# Pucati.net
KiCad netlist of a schematic drawn in EAGLE
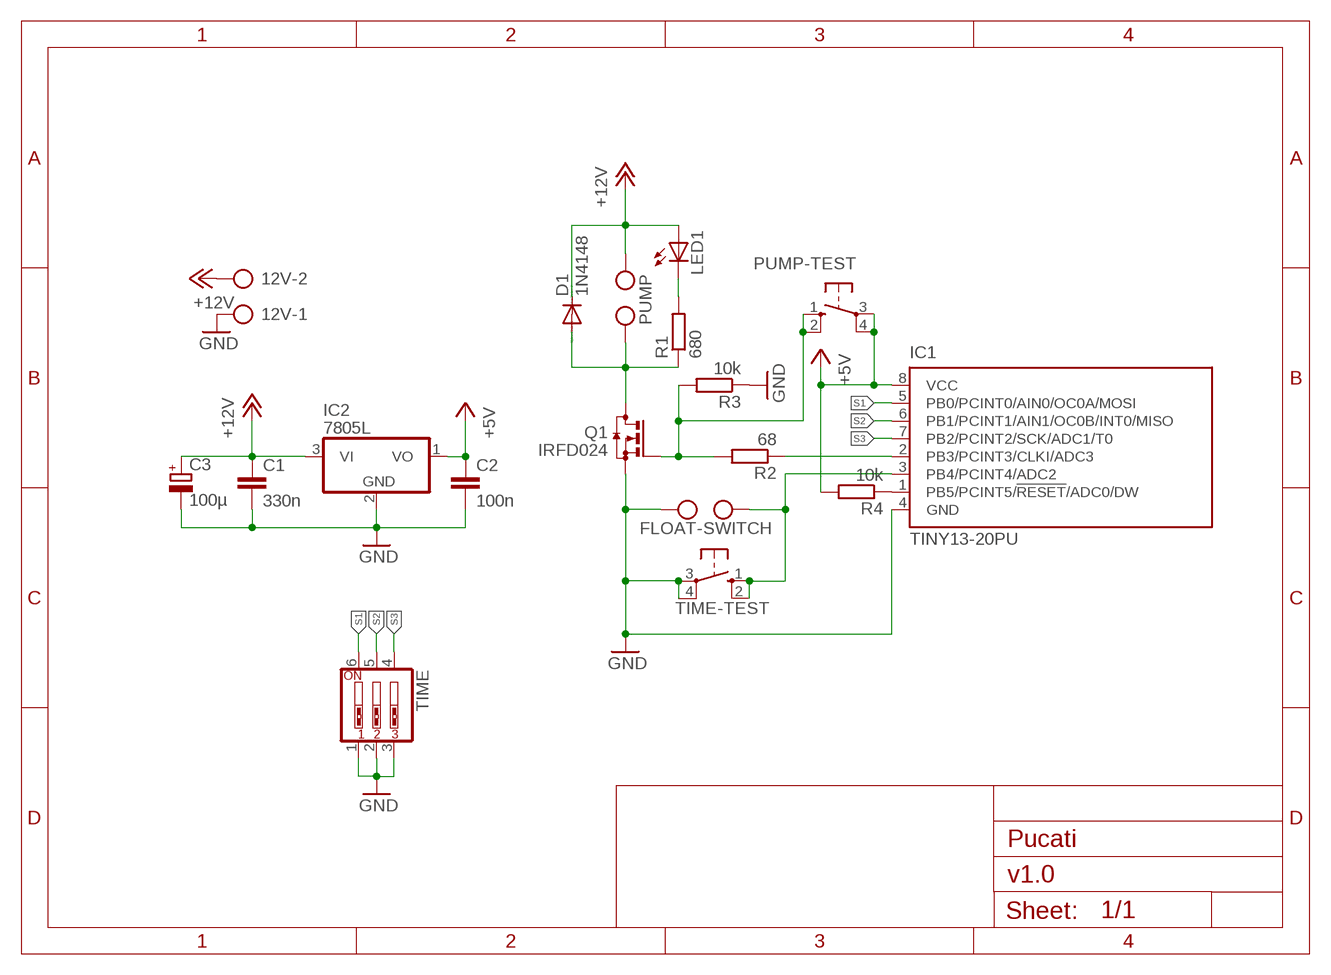
[diagram p0: schematic, sheet 1]

(export (version "E")
  (design (tool "Eeschema 10.0.6"))
  (components
    (comp (ref "12V")
      (value "AK500/2")
      (footprint "eagle-import:AK500_2")
      (libsource (lib "eagle-import") (part "AK500/2"))
    )
    (comp (ref "C1")
      (value "330n")
      (footprint "eagle-import:C1206")
      (libsource (lib "eagle-import") (part "C-EUC1206"))
    )
    (comp (ref "C2")
      (value "100n")
      (footprint "eagle-import:C1206")
      (libsource (lib "eagle-import") (part "C-EUC1206"))
    )
    (comp (ref "C3")
      (value "100µ")
      (footprint "eagle-import:E2,5-5")
      (libsource (lib "eagle-import") (part "CPOL-EUE2.5-5"))
    )
    (comp (ref "D1")
      (value "1N4148")
      (footprint "eagle-import:DO35-10")
      (libsource (lib "eagle-import") (part "1N4148DO35-10"))
    )
    (comp (ref "FLOAT-SWITCH")
      (value "AK500/2")
      (footprint "eagle-import:AK500_2")
      (libsource (lib "eagle-import") (part "AK500/2"))
    )
    (comp (ref "IC1")
      (value "TINY13-20PU")
      (footprint "eagle-import:DIL08")
      (fields (field (name "MPN") "ATTINY13-20PU"))
      (libsource (lib "eagle-import") (part "TINY13PU-20"))
    )
    (comp (ref "IC2")
      (value "7805L")
      (footprint "eagle-import:TO92")
      (libsource (lib "eagle-import") (part "78L05"))
    )
    (comp (ref "LED1")
      (value "LED5MM")
      (footprint "eagle-import:LED5MM")
      (libsource (lib "eagle-import") (part "LED5MM"))
    )
    (comp (ref "PUMP")
      (value "AK500/2")
      (footprint "eagle-import:AK500_2")
      (libsource (lib "eagle-import") (part "AK500/2"))
    )
    (comp (ref "PUMP-TEST")
      (value "10-XX")
      (footprint "eagle-import:B3F-10XX")
      (fields (field (name "MPN") "B3F-1000"))
      (libsource (lib "eagle-import") (part "10-XX"))
    )
    (comp (ref "Q1")
      (value "IRFD024")
      (footprint "eagle-import:C370-01")
      (libsource (lib "eagle-import") (part "IRFD024"))
    )
    (comp (ref "R1")
      (value "680")
      (footprint "eagle-import:R1206")
      (libsource (lib "eagle-import") (part "R-EU_R1206"))
    )
    (comp (ref "R2")
      (value "68")
      (footprint "eagle-import:R1206")
      (libsource (lib "eagle-import") (part "R-EU_R1206"))
    )
    (comp (ref "R3")
      (value "10k")
      (footprint "eagle-import:R1206")
      (libsource (lib "eagle-import") (part "R-EU_R1206"))
    )
    (comp (ref "R4")
      (value "10k")
      (footprint "eagle-import:R1206")
      (libsource (lib "eagle-import") (part "R-EU_R1206"))
    )
    (comp (ref "TIME")
      (value "SW_DIP-3")
      (footprint "eagle-import:EDG-03")
      (libsource (lib "eagle-import") (part "SW_DIP-3"))
    )
    (comp (ref "TIME-TEST")
      (value "10-XX")
      (footprint "eagle-import:B3F-10XX")
      (fields (field (name "MPN") "B3F-1000"))
      (libsource (lib "eagle-import") (part "10-XX"))
    )
  )
  (nets
    (net (code "1") (name "+5V") (class "Default")
      (node (ref "C2") (pin "1") (pinfunction "1_1") (pintype "passive"))
      (node (ref "IC1") (pin "8") (pinfunction "VCC_8") (pintype "power_in"))
      (node (ref "IC2") (pin "1") (pinfunction "VO_1") (pintype "passive"))
      (node (ref "PUMP-TEST") (pin "3") (pinfunction "P_3") (pintype "passive"))
      (node (ref "PUMP-TEST") (pin "4") (pinfunction "P1_4") (pintype "passive"))
      (node (ref "R4") (pin "2") (pinfunction "2_2") (pintype "passive"))
    )
    (net (code "2") (name "+12V") (class "Default")
      (node (ref "12V") (pin "2") (pinfunction "KL_2") (pintype "passive"))
      (node (ref "C1") (pin "1") (pinfunction "1_1") (pintype "passive"))
      (node (ref "C3") (pin "+") (pinfunction "+_+") (pintype "passive"))
      (node (ref "D1") (pin "C") (pinfunction "C_C") (pintype "passive"))
      (node (ref "IC2") (pin "3") (pinfunction "VI_3") (pintype "input"))
      (node (ref "LED1") (pin "A") (pinfunction "A_A") (pintype "passive"))
      (node (ref "PUMP") (pin "2") (pinfunction "KL_2") (pintype "passive"))
    )
    (net (code "3") (name "GND") (class "Default")
      (node (ref "12V") (pin "1") (pinfunction "KL_1") (pintype "passive"))
      (node (ref "C1") (pin "2") (pinfunction "2_2") (pintype "passive"))
      (node (ref "C2") (pin "2") (pinfunction "2_2") (pintype "passive"))
      (node (ref "C3") (pin "-") (pinfunction "-_-") (pintype "passive"))
      (node (ref "FLOAT-SWITCH") (pin "2") (pinfunction "KL_2") (pintype "passive"))
      (node (ref "IC1") (pin "4") (pinfunction "GND_4") (pintype "power_in"))
      (node (ref "IC2") (pin "2") (pinfunction "GND_2") (pintype "passive"))
      (node (ref "Q1") (pin "S") (pinfunction "S_S") (pintype "passive"))
      (node (ref "R3") (pin "1") (pinfunction "1_1") (pintype "passive"))
      (node (ref "TIME") (pin "1") (pinfunction "1_1") (pintype "passive"))
      (node (ref "TIME") (pin "2") (pinfunction "2_2") (pintype "passive"))
      (node (ref "TIME") (pin "3") (pinfunction "3_3") (pintype "passive"))
      (node (ref "TIME-TEST") (pin "3") (pinfunction "P_3") (pintype "passive"))
      (node (ref "TIME-TEST") (pin "4") (pinfunction "P1_4") (pintype "passive"))
    )
    (net (code "4") (name "Net-(FLOAT-SWITCHA-KL)") (class "Default")
      (node (ref "FLOAT-SWITCH") (pin "1") (pinfunction "KL_1") (pintype "passive"))
      (node (ref "IC1") (pin "3") (pinfunction "PB4/PCINT4/ADC2_3") (pintype "bidirectional"))
      (node (ref "TIME-TEST") (pin "1") (pinfunction "S_1") (pintype "passive"))
      (node (ref "TIME-TEST") (pin "2") (pinfunction "S1_2") (pintype "passive"))
    )
    (net (code "5") (name "Net-(IC1-PB3{slash}PCINT3{slash}CLKI{slash}ADC3)") (class "Default")
      (node (ref "IC1") (pin "2") (pinfunction "PB3/PCINT3/CLKI/ADC3_2") (pintype "bidirectional"))
      (node (ref "R2") (pin "1") (pinfunction "1_1") (pintype "passive"))
    )
    (net (code "6") (name "Net-(IC1-PB5{slash}PCINT5{slash}~{RESET}{slash}ADC0{slash}DW)") (class "Default")
      (node (ref "IC1") (pin "1") (pinfunction "PB5/PCINT5/~{RESET}/ADC0/DW_1") (pintype "bidirectional"))
      (node (ref "R4") (pin "1") (pinfunction "1_1") (pintype "passive"))
    )
    (net (code "7") (name "Net-(LED1-C)") (class "Default")
      (node (ref "LED1") (pin "K") (pinfunction "C_K") (pintype "passive"))
      (node (ref "R1") (pin "2") (pinfunction "2_2") (pintype "passive"))
    )
    (net (code "8") (name "Net-(PUMP-TEST-S)") (class "Default")
      (node (ref "PUMP-TEST") (pin "1") (pinfunction "S_1") (pintype "passive"))
      (node (ref "PUMP-TEST") (pin "2") (pinfunction "S1_2") (pintype "passive"))
      (node (ref "Q1") (pin "G") (pinfunction "G_G") (pintype "passive"))
      (node (ref "R2") (pin "2") (pinfunction "2_2") (pintype "passive"))
      (node (ref "R3") (pin "2") (pinfunction "2_2") (pintype "passive"))
    )
    (net (code "9") (name "Net-(PUMPA-KL)") (class "Default")
      (node (ref "D1") (pin "A") (pinfunction "A_A") (pintype "passive"))
      (node (ref "PUMP") (pin "1") (pinfunction "KL_1") (pintype "passive"))
      (node (ref "Q1") (pin "D") (pinfunction "D_D") (pintype "passive"))
      (node (ref "Q1") (pin "D1") (pinfunction "D_D1") (pintype "passive"))
      (node (ref "R1") (pin "1") (pinfunction "1_1") (pintype "passive"))
    )
    (net (code "10") (name "S1") (class "Default")
      (node (ref "IC1") (pin "5") (pinfunction "PB0/PCINT0/AIN0/OC0A/MOSI_5") (pintype "bidirectional"))
      (node (ref "TIME") (pin "6") (pinfunction "6_6") (pintype "passive"))
    )
    (net (code "11") (name "S2") (class "Default")
      (node (ref "IC1") (pin "6") (pinfunction "PB1/PCINT1/AIN1/OC0B/INT0/MISO_6") (pintype "bidirectional"))
      (node (ref "TIME") (pin "5") (pinfunction "5_5") (pintype "passive"))
    )
    (net (code "12") (name "S3") (class "Default")
      (node (ref "IC1") (pin "7") (pinfunction "PB2/PCINT2/SCK/ADC1/T0_7") (pintype "bidirectional"))
      (node (ref "TIME") (pin "4") (pinfunction "4_4") (pintype "passive"))
    )
  )
)
